# DASH_SWITCHES.net
KiCad netlist of a schematic drawn in Altium Designer
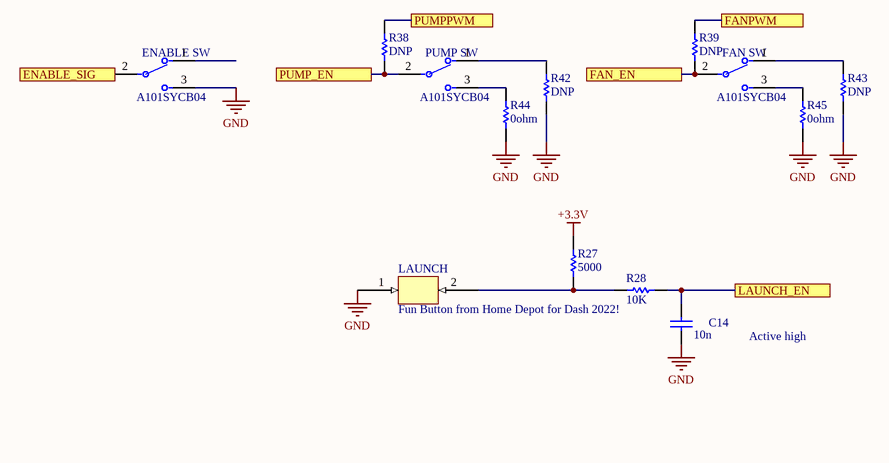
[diagram p0: DASH_SWITCHES.SchDoc]

(export (version "E")
  (design (tool "Eeschema 10.0.6"))
  (components
    (comp (ref "C14")
      (value "10n")
      (footprint "CAPC1608X90X35ML10T15")
      (description "Chip Capacitor, 10 nF, +/- 10%, 50 V, -55 to 125 degC, 0603 (1608 Metric), RoHS, Tape and Reel")
      (fields (field (name "VOLTAGE") "50V") (field (name "TOLERANCE") "10%"))
      (libsource (lib "Altium Content Vault") (part "CAP-NP-2"))
    )
    (comp (ref "ENABLE SW")
      (value "A101SYCB04")
      (footprint "FP-A101SYCB04-MFG")
      (description "SWITCH TOGGLE SPDT 0.4VA 20V")
      (libsource (lib "Altium Content Vault") (part "52c419afdc2a387c7d548259a9aeefb"))
    )
    (comp (ref "FAN SW")
      (value "A101SYCB04")
      (footprint "FP-A101SYCB04-MFG")
      (description "SWITCH TOGGLE SPDT 0.4VA 20V")
      (libsource (lib "Altium Content Vault") (part "52c419afdc2a387c7d548259a9aeefb"))
    )
    (comp (ref "LAUNCH")
      (value "Fun Button from Home Depot for Dash 2022!")
      (footprint "New footprint 1")
      (libsource (lib "Illini Formula Electric") (part "New symbol 1"))
    )
    (comp (ref "PUMP SW")
      (value "A101SYCB04")
      (footprint "FP-A101SYCB04-MFG")
      (description "SWITCH TOGGLE SPDT 0.4VA 20V")
      (libsource (lib "Altium Content Vault") (part "52c419afdc2a387c7d548259a9aeefb"))
    )
    (comp (ref "R27")
      (value "5000")
      (footprint "RESC1608X55X25ML10T15")
      (description "Chip Resistor, 0 Ohm, 0.1 W, -55 to 155 degC, 0603 (1608 Metric)")
      (libsource (lib "Illini Formula Electric") (part "Symbol"))
    )
    (comp (ref "R28")
      (value "10K")
      (footprint "RESC1608X55X25ML10T15")
      (description "Chip Resistor, 0 Ohm, 0.1 W, -55 to 155 degC, 0603 (1608 Metric)")
      (libsource (lib "Illini Formula Electric") (part "Symbol"))
    )
    (comp (ref "R38")
      (value "DNP")
      (footprint "RESC1608X55X25ML10T15")
      (libsource (lib "Illini Formula Electric") (part "Symbol"))
    )
    (comp (ref "R39")
      (value "DNP")
      (footprint "RESC1608X55X25ML10T15")
      (libsource (lib "Illini Formula Electric") (part "Symbol"))
    )
    (comp (ref "R42")
      (value "DNP")
      (footprint "RESC1608X55X25ML10T15")
      (libsource (lib "Illini Formula Electric") (part "Symbol"))
    )
    (comp (ref "R43")
      (value "DNP")
      (footprint "RESC1608X55X25ML10T15")
      (libsource (lib "Illini Formula Electric") (part "Symbol"))
    )
    (comp (ref "R44")
      (value "0ohm")
      (footprint "RESC1608X55X25ML10T15")
      (libsource (lib "Illini Formula Electric") (part "Symbol"))
    )
    (comp (ref "R45")
      (value "0ohm")
      (footprint "RESC1608X55X25ML10T15")
      (libsource (lib "Illini Formula Electric") (part "Symbol"))
    )
  )
  (nets
    (net (code "1") (name "+3.3V") (class "Default")
      (node (ref "R27") (pin "2") (pinfunction "2_2") (pintype "passive"))
    )
    (net (code "2") (name "/ENABLE_SIG") (class "Default")
      (node (ref "ENABLE SW") (pin "2") (pinfunction "2_2") (pintype "passive"))
    )
    (net (code "3") (name "/FANPWM") (class "Default")
      (node (ref "R39") (pin "2") (pinfunction "2_2") (pintype "passive"))
    )
    (net (code "4") (name "/FAN_EN") (class "Default")
      (node (ref "FAN SW") (pin "2") (pinfunction "2_2") (pintype "passive"))
      (node (ref "R39") (pin "1") (pinfunction "1_1") (pintype "passive"))
    )
    (net (code "5") (name "/LAUNCH_EN") (class "Default")
      (node (ref "C14") (pin "2") (pinfunction "2_2") (pintype "passive"))
      (node (ref "R28") (pin "2") (pinfunction "2_2") (pintype "passive"))
    )
    (net (code "6") (name "/PUMPPWM") (class "Default")
      (node (ref "R38") (pin "2") (pinfunction "2_2") (pintype "passive"))
    )
    (net (code "7") (name "/PUMP_EN") (class "Default")
      (node (ref "PUMP SW") (pin "2") (pinfunction "2_2") (pintype "passive"))
      (node (ref "R38") (pin "1") (pinfunction "1_1") (pintype "passive"))
    )
    (net (code "8") (name "GND") (class "Default")
      (node (ref "C14") (pin "1") (pinfunction "1_1") (pintype "passive"))
      (node (ref "ENABLE SW") (pin "3") (pinfunction "3_3") (pintype "passive"))
      (node (ref "LAUNCH") (pin "1") (pintype "input"))
      (node (ref "R42") (pin "1") (pinfunction "1_1") (pintype "passive"))
      (node (ref "R43") (pin "1") (pinfunction "1_1") (pintype "passive"))
      (node (ref "R44") (pin "1") (pinfunction "1_1") (pintype "passive"))
      (node (ref "R45") (pin "1") (pinfunction "1_1") (pintype "passive"))
    )
    (net (code "9") (name "Net-(FAN SW-Pad1)") (class "Default")
      (node (ref "FAN SW") (pin "1") (pinfunction "1_1") (pintype "passive"))
      (node (ref "R43") (pin "2") (pinfunction "2_2") (pintype "passive"))
    )
    (net (code "10") (name "Net-(FAN SW-Pad3)") (class "Default")
      (node (ref "FAN SW") (pin "3") (pinfunction "3_3") (pintype "passive"))
      (node (ref "R45") (pin "2") (pinfunction "2_2") (pintype "passive"))
    )
    (net (code "11") (name "Net-(LAUNCH-Pad2)") (class "Default")
      (node (ref "LAUNCH") (pin "2") (pintype "input"))
      (node (ref "R27") (pin "1") (pinfunction "1_1") (pintype "passive"))
      (node (ref "R28") (pin "1") (pinfunction "1_1") (pintype "passive"))
    )
    (net (code "12") (name "Net-(PUMP SW-Pad1)") (class "Default")
      (node (ref "PUMP SW") (pin "1") (pinfunction "1_1") (pintype "passive"))
      (node (ref "R42") (pin "2") (pinfunction "2_2") (pintype "passive"))
    )
    (net (code "13") (name "Net-(PUMP SW-Pad3)") (class "Default")
      (node (ref "PUMP SW") (pin "3") (pinfunction "3_3") (pintype "passive"))
      (node (ref "R44") (pin "2") (pinfunction "2_2") (pintype "passive"))
    )
    (net (code "14") (name "unconnected-(ENABLE SW-Pad1)") (class "Default")
      (node (ref "ENABLE SW") (pin "1") (pinfunction "1_1") (pintype "passive"))
    )
  )
)
